# SCH_Rubber-Ducky_2026-02-24.net
KiCad netlist of a schematic drawn in EasyEDA
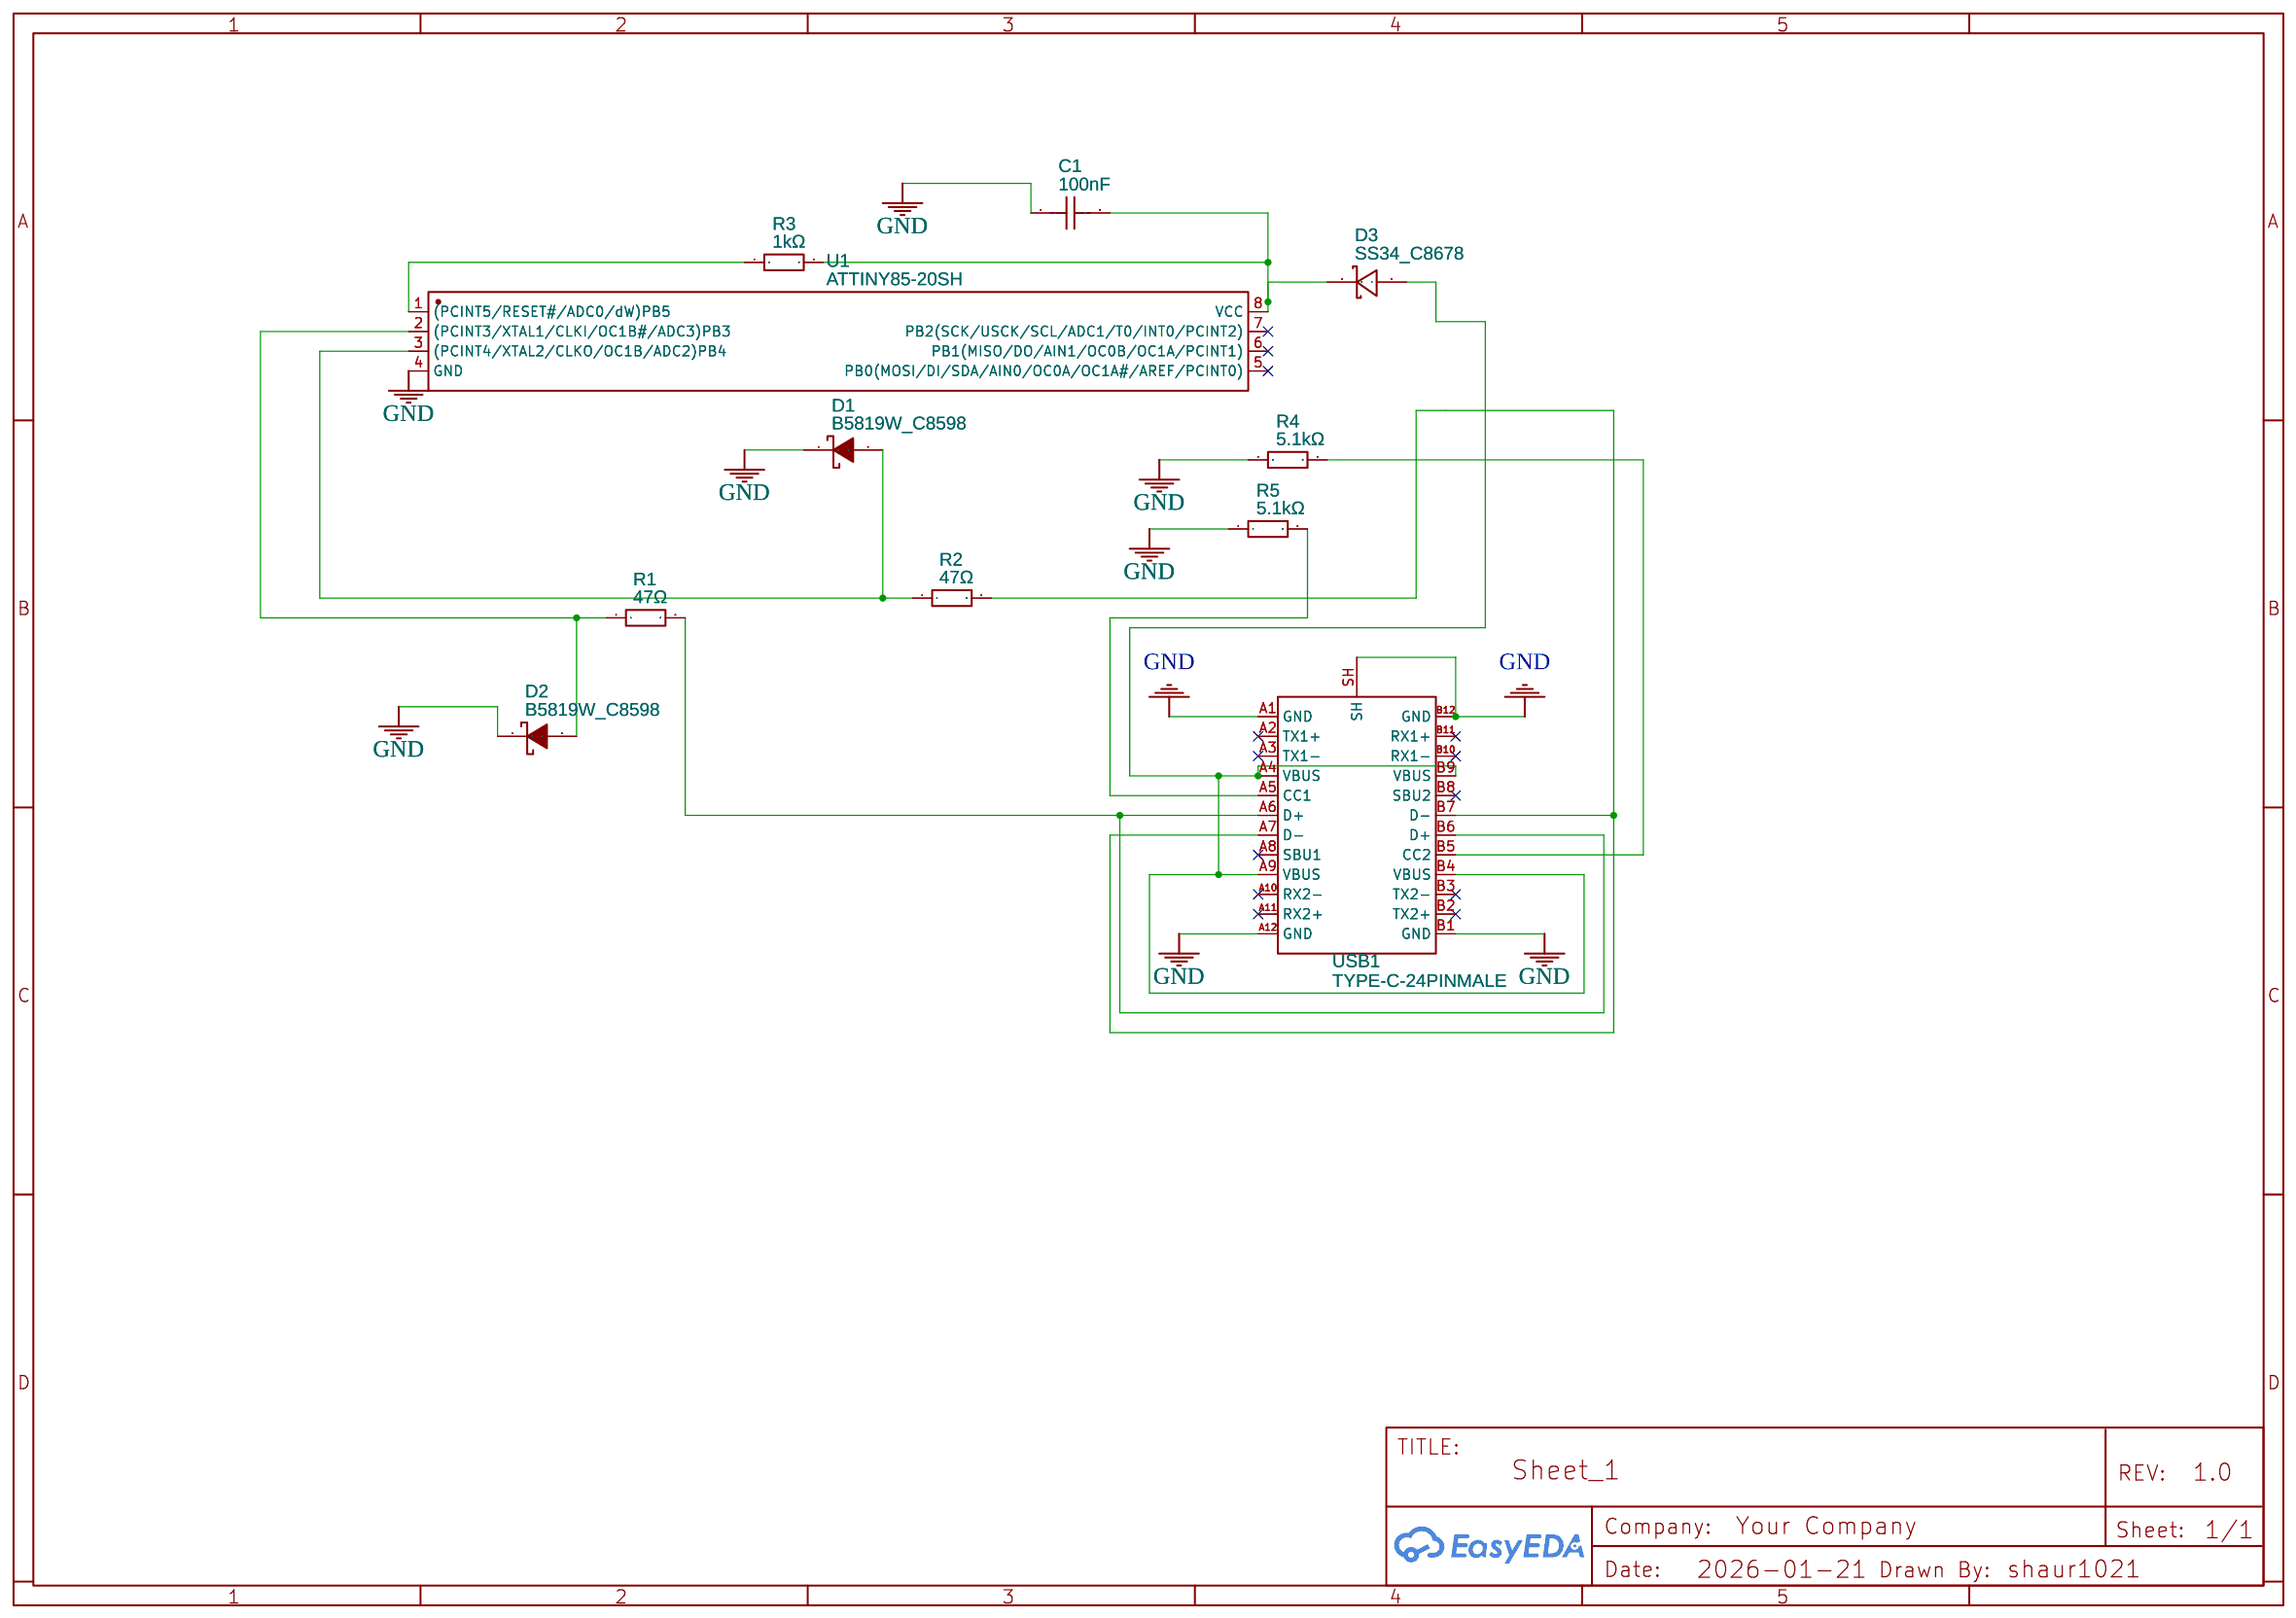
[diagram p0: schematic sheet]

(export (version "E")
  (design (tool "Eeschema 10.0.6"))
  (components
    (comp (ref "C1")
      (value "100nF")
      (fields
        (field (name "Manufacturer Part") "CC0603KRX7R9BB104")
        (field (name "Manufacturer") "YAGEO(国巨)")
      )
      (libsource (lib "") (part "CC0603KRX7R9BB104"))
    )
    (comp (ref "D1")
      (value "B5819W_C8598")
      (fields (field (name "Manufacturer Part") "B5819W SL") (field (name "Manufacturer") "CJ(江苏长电/长晶)"))
      (libsource (lib "") (part "B5819W_C8598"))
    )
    (comp (ref "D2")
      (value "B5819W_C8598")
      (fields (field (name "Manufacturer Part") "B5819W SL") (field (name "Manufacturer") "CJ(江苏长电/长晶)"))
      (libsource (lib "") (part "B5819W_C8598"))
    )
    (comp (ref "D3")
      (value "SS34_C8678")
      (fields (field (name "Manufacturer Part") "SS34") (field (name "Manufacturer") "MDD(辰达半导体)"))
      (libsource (lib "") (part "SS34_C8678"))
    )
    (comp (ref "R1")
      (value "47Ω")
      (fields
        (field (name "Manufacturer Part") "0402WGF470JTCE")
        (field (name "Manufacturer") "UNI-ROYAL(厚声)")
      )
      (libsource (lib "") (part "0402WGF470JTCE"))
    )
    (comp (ref "R2")
      (value "47Ω")
      (fields
        (field (name "Manufacturer Part") "0402WGF470JTCE")
        (field (name "Manufacturer") "UNI-ROYAL(厚声)")
      )
      (libsource (lib "") (part "0402WGF470JTCE"))
    )
    (comp (ref "R3")
      (value "1kΩ")
      (fields
        (field (name "Manufacturer Part") "0603WAF1001T5E")
        (field (name "Manufacturer") "UNI-ROYAL(厚声)")
      )
      (libsource (lib "") (part "0603WAF1001T5E"))
    )
    (comp (ref "R4")
      (value "5.1kΩ")
      (fields
        (field (name "Manufacturer Part") "0603WAF5101T5E")
        (field (name "Manufacturer") "UNI-ROYAL(厚声)")
      )
      (libsource (lib "") (part "0603WAF5101T5E"))
    )
    (comp (ref "R5")
      (value "5.1kΩ")
      (fields
        (field (name "Manufacturer Part") "0603WAF5101T5E")
        (field (name "Manufacturer") "UNI-ROYAL(厚声)")
      )
      (libsource (lib "") (part "0603WAF5101T5E"))
    )
    (comp (ref "U1")
      (value "ATTINY85-20SH")
      (fields (field (name "Manufacturer") "MICROCHIP(美国微芯)"))
      (libsource (lib "") (part "ATTINY85-20SH"))
    )
    (comp (ref "USB1") (value "TYPE-C-24PINMALE") (libsource (lib "") (part "TYPE-C-24PINMALE")))
  )
  (nets
    (net (code "1") (name "GND") (class "Default")
      (node (ref "C1") (pin "1") (pinfunction "1_1") (pintype "unspecified"))
      (node (ref "D1") (pin "1") (pinfunction "-_1") (pintype "unspecified"))
      (node (ref "D2") (pin "1") (pinfunction "-_1") (pintype "unspecified"))
      (node (ref "R4") (pin "1") (pinfunction "1_1") (pintype "input"))
      (node (ref "R5") (pin "1") (pinfunction "1_1") (pintype "input"))
      (node (ref "U1") (pin "4") (pinfunction "GND_4") (pintype "unspecified"))
      (node (ref "USB1") (pin "A1") (pinfunction "GND_A1") (pintype "unspecified"))
      (node (ref "USB1") (pin "A12") (pinfunction "GND_A12") (pintype "unspecified"))
      (node (ref "USB1") (pin "B1") (pinfunction "GND_B1") (pintype "unspecified"))
      (node (ref "USB1") (pin "B12") (pinfunction "GND_B12") (pintype "unspecified"))
      (node (ref "USB1") (pin "SH") (pinfunction "SH_SH") (pintype "unspecified"))
    )
    (net (code "2") (name "Net-(D1-+)") (class "Default")
      (node (ref "D1") (pin "2") (pinfunction "+_2") (pintype "unspecified"))
      (node (ref "R2") (pin "1") (pinfunction "1_1") (pintype "input"))
      (node (ref "U1") (pin "3") (pinfunction "(PCINT4/XTAL2/CLKO/OC1B/ADC2)PB4_3") (pintype "unspecified"))
    )
    (net (code "3") (name "Net-(D2-+)") (class "Default")
      (node (ref "D2") (pin "2") (pinfunction "+_2") (pintype "unspecified"))
      (node (ref "R1") (pin "1") (pinfunction "1_1") (pintype "input"))
      (node (ref "U1") (pin "2") (pinfunction "(PCINT3/XTAL1/CLKI/OC1B#/ADC3)PB3_2") (pintype "unspecified"))
    )
    (net (code "4") (name "Net-(D3-A)") (class "Default")
      (node (ref "D3") (pin "2") (pinfunction "A_2") (pintype "unspecified"))
      (node (ref "USB1") (pin "A4") (pinfunction "VBUS_A4") (pintype "unspecified"))
      (node (ref "USB1") (pin "A9") (pinfunction "VBUS_A9") (pintype "unspecified"))
      (node (ref "USB1") (pin "B4") (pinfunction "VBUS_B4") (pintype "unspecified"))
      (node (ref "USB1") (pin "B9") (pinfunction "VBUS_B9") (pintype "unspecified"))
    )
    (net (code "5") (name "Net-(D3-K)") (class "Default")
      (node (ref "C1") (pin "2") (pinfunction "2_2") (pintype "unspecified"))
      (node (ref "D3") (pin "1") (pinfunction "K_1") (pintype "unspecified"))
      (node (ref "R3") (pin "2") (pinfunction "2_2") (pintype "input"))
      (node (ref "U1") (pin "8") (pinfunction "VCC_8") (pintype "unspecified"))
    )
    (net (code "6") (name "Net-(R1-Pad2)") (class "Default")
      (node (ref "R1") (pin "2") (pinfunction "2_2") (pintype "input"))
      (node (ref "USB1") (pin "A6") (pinfunction "D+_A6") (pintype "unspecified"))
      (node (ref "USB1") (pin "B6") (pinfunction "D+_B6") (pintype "unspecified"))
    )
    (net (code "7") (name "Net-(R2-Pad2)") (class "Default")
      (node (ref "R2") (pin "2") (pinfunction "2_2") (pintype "input"))
      (node (ref "USB1") (pin "A7") (pinfunction "D-_A7") (pintype "unspecified"))
      (node (ref "USB1") (pin "B7") (pinfunction "D-_B7") (pintype "unspecified"))
    )
    (net (code "8") (name "Net-(U1-(PCINT5{slash}RESET#{slash}ADC0{slash}dW)PB5)") (class "Default")
      (node (ref "R3") (pin "1") (pinfunction "1_1") (pintype "input"))
      (node (ref "U1") (pin "1") (pinfunction "(PCINT5/RESET#/ADC0/dW)PB5_1") (pintype "unspecified"))
    )
    (net (code "9") (name "Net-(USB1-CC1)") (class "Default")
      (node (ref "R5") (pin "2") (pinfunction "2_2") (pintype "input"))
      (node (ref "USB1") (pin "A5") (pinfunction "CC1_A5") (pintype "unspecified"))
    )
    (net (code "10") (name "Net-(USB1-CC2)") (class "Default")
      (node (ref "R4") (pin "2") (pinfunction "2_2") (pintype "input"))
      (node (ref "USB1") (pin "B5") (pinfunction "CC2_B5") (pintype "unspecified"))
    )
    (net (code "11") (name "unconnected-(U1-PB0(MOSI{slash}DI{slash}SDA{slash}AIN0{slash}OC0A{slash}OC1A#{slash}AREF{slash}PCINT0)-Pad5)") (class "Default")
      (node (ref "U1") (pin "5") (pinfunction "PB0(MOSI/DI/SDA/AIN0/OC0A/OC1A#/AREF/PCINT0)_5") (pintype "unspecified+no_connect"))
    )
    (net (code "12") (name "unconnected-(U1-PB1(MISO{slash}DO{slash}AIN1{slash}OC0B{slash}OC1A{slash}PCINT1)-Pad6)") (class "Default")
      (node (ref "U1") (pin "6") (pinfunction "PB1(MISO/DO/AIN1/OC0B/OC1A/PCINT1)_6") (pintype "unspecified+no_connect"))
    )
    (net (code "13") (name "unconnected-(U1-PB2(SCK{slash}USCK{slash}SCL{slash}ADC1{slash}T0{slash}INT0{slash}PCINT2)-Pad7)") (class "Default")
      (node (ref "U1") (pin "7") (pinfunction "PB2(SCK/USCK/SCL/ADC1/T0/INT0/PCINT2)_7") (pintype "unspecified+no_connect"))
    )
    (net (code "14") (name "unconnected-(USB1-RX1+-PadB11)") (class "Default")
      (node (ref "USB1") (pin "B11") (pinfunction "RX1+_B11") (pintype "unspecified+no_connect"))
    )
    (net (code "15") (name "unconnected-(USB1-RX1--PadB10)") (class "Default")
      (node (ref "USB1") (pin "B10") (pinfunction "RX1-_B10") (pintype "unspecified+no_connect"))
    )
    (net (code "16") (name "unconnected-(USB1-RX2+-PadA11)") (class "Default")
      (node (ref "USB1") (pin "A11") (pinfunction "RX2+_A11") (pintype "unspecified+no_connect"))
    )
    (net (code "17") (name "unconnected-(USB1-RX2--PadA10)") (class "Default")
      (node (ref "USB1") (pin "A10") (pinfunction "RX2-_A10") (pintype "unspecified+no_connect"))
    )
    (net (code "18") (name "unconnected-(USB1-SBU1-PadA8)") (class "Default")
      (node (ref "USB1") (pin "A8") (pinfunction "SBU1_A8") (pintype "unspecified+no_connect"))
    )
    (net (code "19") (name "unconnected-(USB1-SBU2-PadB8)") (class "Default")
      (node (ref "USB1") (pin "B8") (pinfunction "SBU2_B8") (pintype "unspecified+no_connect"))
    )
    (net (code "20") (name "unconnected-(USB1-TX1+-PadA2)") (class "Default")
      (node (ref "USB1") (pin "A2") (pinfunction "TX1+_A2") (pintype "unspecified+no_connect"))
    )
    (net (code "21") (name "unconnected-(USB1-TX1--PadA3)") (class "Default")
      (node (ref "USB1") (pin "A3") (pinfunction "TX1-_A3") (pintype "unspecified+no_connect"))
    )
    (net (code "22") (name "unconnected-(USB1-TX2+-PadB2)") (class "Default")
      (node (ref "USB1") (pin "B2") (pinfunction "TX2+_B2") (pintype "unspecified+no_connect"))
    )
    (net (code "23") (name "unconnected-(USB1-TX2--PadB3)") (class "Default")
      (node (ref "USB1") (pin "B3") (pinfunction "TX2-_B3") (pintype "unspecified+no_connect"))
    )
  )
)
